# satellite.net
KiCad netlist of a schematic drawn in EAGLE
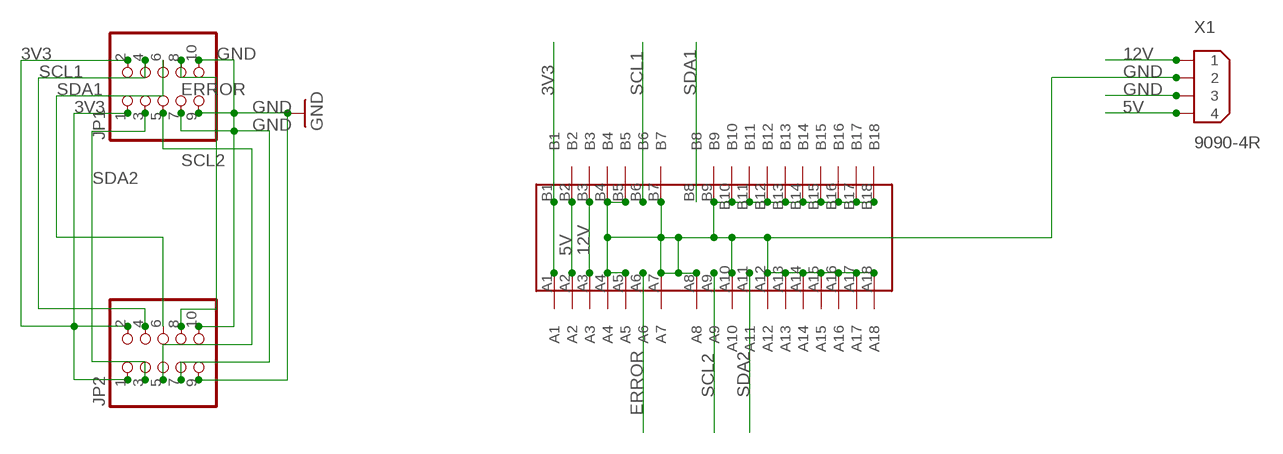
[diagram p0: schematic, sheet 1]

(export (version "E")
  (design (tool "Eeschema 10.0.6"))
  (components
    (comp (ref "JP1")
      (value "PINHD-2X5")
      (footprint "eagle-import:2X05")
      (libsource (lib "eagle-import") (part "PINHD-2X5"))
    )
    (comp (ref "JP2")
      (value "PINHD-2X5")
      (footprint "eagle-import:2X05")
      (libsource (lib "eagle-import") (part "PINHD-2X5"))
    )
    (comp (ref "U$1")
      (value "PCIE1X")
      (footprint "eagle-import:PCIE1X")
      (libsource (lib "eagle-import") (part "PCIE1X"))
    )
    (comp (ref "X1")
      (value "9090-4R")
      (footprint "eagle-import:9090-4R")
      (libsource (lib "eagle-import") (part "9090-4R"))
    )
  )
  (nets
    (net (code "1") (name "/3V3") (class "Default")
      (node (ref "JP1") (pin "1") (pinfunction "1_1") (pintype "passive"))
      (node (ref "JP1") (pin "2") (pinfunction "2_2") (pintype "passive"))
      (node (ref "JP2") (pin "1") (pinfunction "1_1") (pintype "passive"))
      (node (ref "JP2") (pin "2") (pinfunction "2_2") (pintype "passive"))
      (node (ref "U$1") (pin "A1") (pinfunction "A1_A1") (pintype "bidirectional"))
      (node (ref "U$1") (pin "B1") (pinfunction "B1_B1") (pintype "bidirectional"))
    )
    (net (code "2") (name "/5V") (class "Default")
      (node (ref "U$1") (pin "A2") (pinfunction "A2_A2") (pintype "bidirectional"))
      (node (ref "U$1") (pin "B2") (pinfunction "B2_B2") (pintype "bidirectional"))
      (node (ref "X1") (pin "4") (pinfunction "4_4") (pintype "passive"))
    )
    (net (code "3") (name "/12V") (class "Default")
      (node (ref "U$1") (pin "A3") (pinfunction "A3_A3") (pintype "bidirectional"))
      (node (ref "U$1") (pin "B3") (pinfunction "B3_B3") (pintype "bidirectional"))
      (node (ref "X1") (pin "1") (pinfunction "1_1") (pintype "passive"))
    )
    (net (code "4") (name "/ERROR") (class "Default")
      (node (ref "JP1") (pin "8") (pinfunction "8_8") (pintype "passive"))
      (node (ref "JP2") (pin "8") (pinfunction "8_8") (pintype "passive"))
      (node (ref "U$1") (pin "A6") (pinfunction "A6_A6") (pintype "bidirectional"))
    )
    (net (code "5") (name "/SCL1") (class "Default")
      (node (ref "JP1") (pin "4") (pinfunction "4_4") (pintype "passive"))
      (node (ref "JP2") (pin "4") (pinfunction "4_4") (pintype "passive"))
      (node (ref "U$1") (pin "B6") (pinfunction "B6_B6") (pintype "bidirectional"))
    )
    (net (code "6") (name "/SCL2") (class "Default")
      (node (ref "JP1") (pin "5") (pinfunction "5_5") (pintype "passive"))
      (node (ref "JP2") (pin "5") (pinfunction "5_5") (pintype "passive"))
      (node (ref "U$1") (pin "A9") (pinfunction "A9_A9") (pintype "bidirectional"))
    )
    (net (code "7") (name "/SDA1") (class "Default")
      (node (ref "JP1") (pin "6") (pinfunction "6_6") (pintype "passive"))
      (node (ref "JP2") (pin "6") (pinfunction "6_6") (pintype "passive"))
      (node (ref "U$1") (pin "B8") (pinfunction "B8_B8") (pintype "bidirectional"))
    )
    (net (code "8") (name "/SDA2") (class "Default")
      (node (ref "JP1") (pin "3") (pinfunction "3_3") (pintype "passive"))
      (node (ref "JP2") (pin "3") (pinfunction "3_3") (pintype "passive"))
      (node (ref "U$1") (pin "A11") (pinfunction "A11_A11") (pintype "bidirectional"))
    )
    (net (code "9") (name "GND") (class "Default")
      (node (ref "JP1") (pin "10") (pinfunction "10_10") (pintype "passive"))
      (node (ref "JP1") (pin "7") (pinfunction "7_7") (pintype "passive"))
      (node (ref "JP1") (pin "9") (pinfunction "9_9") (pintype "passive"))
      (node (ref "JP2") (pin "10") (pinfunction "10_10") (pintype "passive"))
      (node (ref "JP2") (pin "7") (pinfunction "7_7") (pintype "passive"))
      (node (ref "JP2") (pin "9") (pinfunction "9_9") (pintype "passive"))
      (node (ref "U$1") (pin "A10") (pinfunction "A10_A10") (pintype "bidirectional"))
      (node (ref "U$1") (pin "A12") (pinfunction "A12_A12") (pintype "bidirectional"))
      (node (ref "U$1") (pin "A13") (pinfunction "A13_A13") (pintype "bidirectional"))
      (node (ref "U$1") (pin "A14") (pinfunction "A14_A14") (pintype "bidirectional"))
      (node (ref "U$1") (pin "A15") (pinfunction "A15_A15") (pintype "bidirectional"))
      (node (ref "U$1") (pin "A16") (pinfunction "A16_A16") (pintype "bidirectional"))
      (node (ref "U$1") (pin "A17") (pinfunction "A17_A17") (pintype "bidirectional"))
      (node (ref "U$1") (pin "A18") (pinfunction "A18_A18") (pintype "bidirectional"))
      (node (ref "U$1") (pin "A4") (pinfunction "A4_A4") (pintype "bidirectional"))
      (node (ref "U$1") (pin "A5") (pinfunction "A5_A5") (pintype "bidirectional"))
      (node (ref "U$1") (pin "A7") (pinfunction "A7_A7") (pintype "bidirectional"))
      (node (ref "U$1") (pin "A8") (pinfunction "A8_A8") (pintype "bidirectional"))
      (node (ref "U$1") (pin "B10") (pinfunction "B10_B10") (pintype "bidirectional"))
      (node (ref "U$1") (pin "B11") (pinfunction "B11_B11") (pintype "bidirectional"))
      (node (ref "U$1") (pin "B12") (pinfunction "B12_B12") (pintype "bidirectional"))
      (node (ref "U$1") (pin "B13") (pinfunction "B13_B13") (pintype "bidirectional"))
      (node (ref "U$1") (pin "B14") (pinfunction "B14_B14") (pintype "bidirectional"))
      (node (ref "U$1") (pin "B15") (pinfunction "B15_B15") (pintype "bidirectional"))
      (node (ref "U$1") (pin "B16") (pinfunction "B16_B16") (pintype "bidirectional"))
      (node (ref "U$1") (pin "B17") (pinfunction "B17_B17") (pintype "bidirectional"))
      (node (ref "U$1") (pin "B18") (pinfunction "B18_B18") (pintype "bidirectional"))
      (node (ref "U$1") (pin "B4") (pinfunction "B4_B4") (pintype "bidirectional"))
      (node (ref "U$1") (pin "B5") (pinfunction "B5_B5") (pintype "bidirectional"))
      (node (ref "U$1") (pin "B7") (pinfunction "B7_B7") (pintype "bidirectional"))
      (node (ref "U$1") (pin "B9") (pinfunction "B9_B9") (pintype "bidirectional"))
      (node (ref "X1") (pin "2") (pinfunction "2_2") (pintype "passive"))
      (node (ref "X1") (pin "3") (pinfunction "3_3") (pintype "passive"))
    )
  )
)
